# MCU.net
KiCad netlist of a schematic drawn in Altium Designer
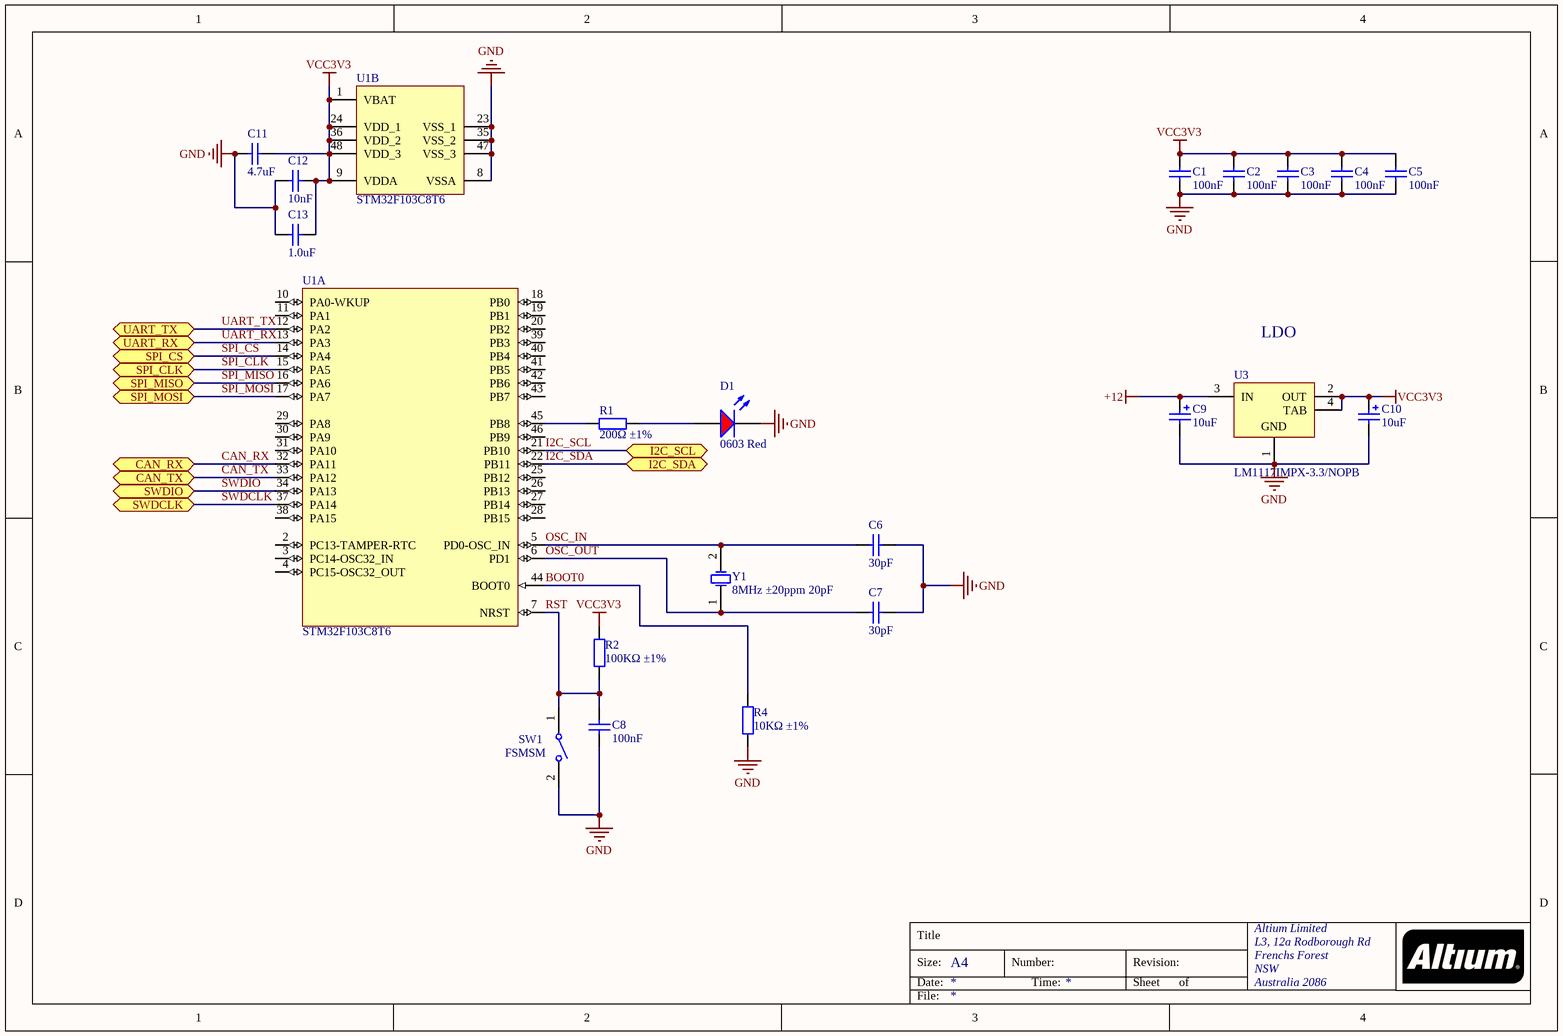
[diagram p0: MCU.SchDoc]

(export (version "E")
  (design (tool "Eeschema 10.0.6"))
  (components
    (comp (ref "C1")
      (value "100nF")
      (footprint "0402_C")
      (description "Chip capacitors")
      (fields
        (field (name "MANUFACTURER") "Samsung Electro-Mechanics")
        (field (name "PARTNUMBER") "CL05B104KO5NNNC")
      )
      (libsource (lib "Miscellaneous Devices LC") (part "0402 100nF (104) 10% 16V"))
    )
    (comp (ref "C2")
      (value "100nF")
      (footprint "0402_C")
      (description "Chip capacitors")
      (fields
        (field (name "MANUFACTURER") "Samsung Electro-Mechanics")
        (field (name "PARTNUMBER") "CL05B104KO5NNNC")
      )
      (libsource (lib "Miscellaneous Devices LC") (part "0402 100nF (104) 10% 16V"))
    )
    (comp (ref "C3")
      (value "100nF")
      (footprint "0402_C")
      (description "Chip capacitors")
      (fields
        (field (name "MANUFACTURER") "Samsung Electro-Mechanics")
        (field (name "PARTNUMBER") "CL05B104KO5NNNC")
      )
      (libsource (lib "Miscellaneous Devices LC") (part "0402 100nF (104) 10% 16V"))
    )
    (comp (ref "C4")
      (value "100nF")
      (footprint "0402_C")
      (description "Chip capacitors")
      (fields
        (field (name "MANUFACTURER") "Samsung Electro-Mechanics")
        (field (name "PARTNUMBER") "CL05B104KO5NNNC")
      )
      (libsource (lib "Miscellaneous Devices LC") (part "0402 100nF (104) 10% 16V"))
    )
    (comp (ref "C5")
      (value "100nF")
      (footprint "0402_C")
      (description "Chip capacitors")
      (fields
        (field (name "MANUFACTURER") "Samsung Electro-Mechanics")
        (field (name "PARTNUMBER") "CL05B104KO5NNNC")
      )
      (libsource (lib "Miscellaneous Devices LC") (part "0402 100nF (104) 10% 16V"))
    )
    (comp (ref "C6")
      (value "30pF")
      (footprint "0402_C")
      (description "Chip capacitors")
      (fields
        (field (name "MANUFACTURER") "Guangdong Fenghua Advanced Tech")
        (field (name "PARTNUMBER") "0402CG300J500NT")
      )
      (libsource (lib "Miscellaneous Devices LC") (part "0402 30pF (300) 5% 50V"))
    )
    (comp (ref "C7")
      (value "30pF")
      (footprint "0402_C")
      (description "Chip capacitors")
      (fields
        (field (name "MANUFACTURER") "Guangdong Fenghua Advanced Tech")
        (field (name "PARTNUMBER") "0402CG300J500NT")
      )
      (libsource (lib "Miscellaneous Devices LC") (part "0402 30pF (300) 5% 50V"))
    )
    (comp (ref "C8")
      (value "100nF")
      (footprint "0402_C")
      (description "Chip capacitors")
      (fields
        (field (name "MANUFACTURER") "Samsung Electro-Mechanics")
        (field (name "PARTNUMBER") "CL05B104KO5NNNC")
      )
      (libsource (lib "Miscellaneous Devices LC") (part "0402 100nF (104) 10% 16V"))
    )
    (comp (ref "C9")
      (value "10uF")
      (footprint "CASE-A_3216")
      (description "Tantalum capacitor")
      (fields (field (name "MANUFACTURER") "AVX") (field (name "PARTNUMBER") "TAJA106K016RNJ"))
      (libsource (lib "Miscellaneous Devices LC") (part "3216 10uF (106) 10% 16V"))
    )
    (comp (ref "C10")
      (value "10uF")
      (footprint "CASE-A_3216")
      (description "Tantalum capacitor")
      (fields (field (name "MANUFACTURER") "AVX") (field (name "PARTNUMBER") "TAJA106K016RNJ"))
      (libsource (lib "Miscellaneous Devices LC") (part "3216 10uF (106) 10% 16V"))
    )
    (comp (ref "C11")
      (value "4.7uF")
      (footprint "0402_C")
      (description "Chip capacitor")
      (fields
        (field (name "MANUFACTURER") "Samsung Electro-Mechanics")
        (field (name "PARTNUMBER") "CL05A475MP5NRNC")
      )
      (libsource (lib "Miscellaneous Devices LC") (part "0402 4.7uF (475) 20% 10V"))
    )
    (comp (ref "C12")
      (value "10nF")
      (footprint "0402_C")
      (description "Chip capacitors")
      (fields
        (field (name "MANUFACTURER") "Samsung Electro-Mechanics")
        (field (name "PARTNUMBER") "CL05B103KB5NNNC")
      )
      (libsource (lib "Miscellaneous Devices LC") (part "0402 10nF (103) 10% 50V"))
    )
    (comp (ref "C13")
      (value "1.0uF")
      (footprint "0402_C")
      (description "Chip capacitor")
      (fields
        (field (name "MANUFACTURER") "Samsung Electro-Mechanics")
        (field (name "PARTNUMBER") "CL05A105KA5NQNC")
      )
      (libsource (lib "Miscellaneous Devices LC") (part "0402 1.0uF (105) 10% 25V"))
    )
    (comp (ref "D1")
      (value "0603 Red")
      (footprint "0603_LED_S1")
      (description "LED")
      (libsource (lib "Miscellaneous Devices LC") (part "0603 LED Red"))
    )
    (comp (ref "R1")
      (value "200Ω ±1%")
      (footprint "0402_R")
      (description "Chip resistor")
      (fields (field (name "MANUFACTURER") "Uniroyal Elec") (field (name "PARTNUMBER") "0402WGF2000TCE"))
      (libsource (lib "Miscellaneous Devices LC") (part "0402 200R (2000) 1%"))
    )
    (comp (ref "R2")
      (value "100KΩ ±1%")
      (footprint "0402_R")
      (description "Chip resistor")
      (fields (field (name "MANUFACTURER") "Uniroyal Elec") (field (name "PARTNUMBER") "0402WGF1003TCE"))
      (libsource (lib "Miscellaneous Devices LC") (part "0402 100K (1003) 1%"))
    )
    (comp (ref "R4")
      (value "10KΩ ±1%")
      (footprint "0402_R")
      (description "Chip resistor")
      (fields (field (name "MANUFACTURER") "Uniroyal Elec") (field (name "PARTNUMBER") "0402WGF1002TCE"))
      (libsource (lib "Miscellaneous Devices LC") (part "0402 10K (1002) 1%"))
    )
    (comp (ref "SW1")
      (value "FSMSM")
      (footprint "TECO-FSMSM-2_V")
      (description "FSMSM Push Button Switch, 50 mA, -35 to 85 degC, 2-Pin SMD, RoHS, Bulk")
      (fields (field (name "MANUFACTURER") "TE Connectivity"))
      (libsource (lib "Altium Content Vault") (part "SW-SPST-2_C"))
    )
    (comp (ref "U1")
      (value "STM32F103C8T6")
      (footprint "LQFP-48_7x7x05P")
      (description "ARM")
      (libsource (lib "Miscellaneous Devices LC") (part "STM32F103C8T6"))
    )
    (comp (ref "U3")
      (value "LM1117IMPX-3.3/NOPB")
      (footprint "MP04A_M")
      (description "800mA Low-Dropout Linear Regulator, 4-pin SOT-223, Pb-Free")
      (fields (field (name "MANUFACTURER") "National Semiconductor"))
      (libsource (lib "Altium Content Vault") (part "PM-REG-LM1086-SOT4"))
    )
    (comp (ref "Y1")
      (value "8MHz ±20ppm 20pF")
      (footprint "SMD-5032_2P")
      (description "贴片晶振")
      (libsource (lib "Miscellaneous Devices LC") (part "SMD-5032_2P 8MHz 20ppm 20pF"))
    )
  )
  (nets
    (net (code "1") (name "+12") (class "Default")
      (node (ref "C9") (pin "1") (pinfunction "1_1") (pintype "passive"))
      (node (ref "U3") (pin "3") (pinfunction "IN_3") (pintype "power_in"))
    )
    (net (code "2") (name "/BOOT0") (class "Default")
      (node (ref "R4") (pin "2") (pinfunction "2_2") (pintype "passive"))
      (node (ref "U1") (pin "44") (pinfunction "BOOT0_44") (pintype "input"))
    )
    (net (code "3") (name "/CAN_RX") (class "Default")
      (node (ref "U1") (pin "32") (pinfunction "PA11_32") (pintype "bidirectional"))
    )
    (net (code "4") (name "/CAN_TX") (class "Default")
      (node (ref "U1") (pin "33") (pinfunction "PA12_33") (pintype "bidirectional"))
    )
    (net (code "5") (name "/I2C_SCL") (class "Default")
      (node (ref "U1") (pin "21") (pinfunction "PB10_21") (pintype "bidirectional"))
    )
    (net (code "6") (name "/I2C_SDA") (class "Default")
      (node (ref "U1") (pin "22") (pinfunction "PB11_22") (pintype "bidirectional"))
    )
    (net (code "7") (name "/OSC_IN") (class "Default")
      (node (ref "C6") (pin "1") (pinfunction "1_1") (pintype "passive"))
      (node (ref "U1") (pin "5") (pinfunction "PD0-OSC_IN_5") (pintype "bidirectional"))
      (node (ref "Y1") (pin "2") (pinfunction "OSC2_2") (pintype "passive"))
    )
    (net (code "8") (name "/OSC_OUT") (class "Default")
      (node (ref "C7") (pin "1") (pinfunction "1_1") (pintype "passive"))
      (node (ref "U1") (pin "6") (pinfunction "PD1_6") (pintype "bidirectional"))
      (node (ref "Y1") (pin "1") (pinfunction "OSC1_1") (pintype "passive"))
    )
    (net (code "9") (name "/RST") (class "Default")
      (node (ref "C8") (pin "2") (pinfunction "2_2") (pintype "passive"))
      (node (ref "R2") (pin "1") (pinfunction "1_1") (pintype "passive"))
      (node (ref "SW1") (pin "1") (pinfunction "1_1") (pintype "passive"))
      (node (ref "U1") (pin "7") (pinfunction "NRST_7") (pintype "bidirectional"))
    )
    (net (code "10") (name "/SPI_CLK") (class "Default")
      (node (ref "U1") (pin "15") (pinfunction "PA5_15") (pintype "bidirectional"))
    )
    (net (code "11") (name "/SPI_CS") (class "Default")
      (node (ref "U1") (pin "14") (pinfunction "PA4_14") (pintype "bidirectional"))
    )
    (net (code "12") (name "/SPI_MISO") (class "Default")
      (node (ref "U1") (pin "16") (pinfunction "PA6_16") (pintype "bidirectional"))
    )
    (net (code "13") (name "/SPI_MOSI") (class "Default")
      (node (ref "U1") (pin "17") (pinfunction "PA7_17") (pintype "bidirectional"))
    )
    (net (code "14") (name "/SWDCLK") (class "Default")
      (node (ref "U1") (pin "37") (pinfunction "PA14_37") (pintype "bidirectional"))
    )
    (net (code "15") (name "/SWDIO") (class "Default")
      (node (ref "U1") (pin "34") (pinfunction "PA13_34") (pintype "bidirectional"))
    )
    (net (code "16") (name "/UART_RX") (class "Default")
      (node (ref "U1") (pin "13") (pinfunction "PA3_13") (pintype "bidirectional"))
    )
    (net (code "17") (name "/UART_TX") (class "Default")
      (node (ref "U1") (pin "12") (pinfunction "PA2_12") (pintype "bidirectional"))
    )
    (net (code "18") (name "GND") (class "Default")
      (node (ref "C1") (pin "1") (pinfunction "1_1") (pintype "passive"))
      (node (ref "C10") (pin "2") (pinfunction "2_2") (pintype "passive"))
      (node (ref "C11") (pin "1") (pinfunction "1_1") (pintype "passive"))
      (node (ref "C12") (pin "1") (pinfunction "1_1") (pintype "passive"))
      (node (ref "C13") (pin "1") (pinfunction "1_1") (pintype "passive"))
      (node (ref "C2") (pin "1") (pinfunction "1_1") (pintype "passive"))
      (node (ref "C3") (pin "1") (pinfunction "1_1") (pintype "passive"))
      (node (ref "C4") (pin "1") (pinfunction "1_1") (pintype "passive"))
      (node (ref "C5") (pin "1") (pinfunction "1_1") (pintype "passive"))
      (node (ref "C6") (pin "2") (pinfunction "2_2") (pintype "passive"))
      (node (ref "C7") (pin "2") (pinfunction "2_2") (pintype "passive"))
      (node (ref "C8") (pin "1") (pinfunction "1_1") (pintype "passive"))
      (node (ref "C9") (pin "2") (pinfunction "2_2") (pintype "passive"))
      (node (ref "D1") (pin "K") (pinfunction "K_K") (pintype "passive"))
      (node (ref "R4") (pin "1") (pinfunction "1_1") (pintype "passive"))
      (node (ref "SW1") (pin "2") (pinfunction "2_2") (pintype "passive"))
      (node (ref "U1") (pin "23") (pinfunction "VSS_1_23") (pintype "power_in"))
      (node (ref "U1") (pin "35") (pinfunction "VSS_2_35") (pintype "power_in"))
      (node (ref "U1") (pin "47") (pinfunction "VSS_3_47") (pintype "power_in"))
      (node (ref "U1") (pin "8") (pinfunction "VSSA_8") (pintype "power_in"))
      (node (ref "U3") (pin "1") (pinfunction "GND_1") (pintype "power_in"))
    )
    (net (code "19") (name "Net-(D1-PadA)") (class "Default")
      (node (ref "D1") (pin "A") (pinfunction "A_A") (pintype "passive"))
      (node (ref "R1") (pin "2") (pinfunction "2_2") (pintype "passive"))
    )
    (net (code "20") (name "Net-(U1A-PB8)") (class "Default")
      (node (ref "R1") (pin "1") (pinfunction "1_1") (pintype "passive"))
      (node (ref "U1") (pin "45") (pinfunction "PB8_45") (pintype "bidirectional"))
    )
    (net (code "21") (name "VCC3V3") (class "Default")
      (node (ref "C1") (pin "2") (pinfunction "2_2") (pintype "passive"))
      (node (ref "C10") (pin "1") (pinfunction "1_1") (pintype "passive"))
      (node (ref "C11") (pin "2") (pinfunction "2_2") (pintype "passive"))
      (node (ref "C12") (pin "2") (pinfunction "2_2") (pintype "passive"))
      (node (ref "C13") (pin "2") (pinfunction "2_2") (pintype "passive"))
      (node (ref "C2") (pin "2") (pinfunction "2_2") (pintype "passive"))
      (node (ref "C3") (pin "2") (pinfunction "2_2") (pintype "passive"))
      (node (ref "C4") (pin "2") (pinfunction "2_2") (pintype "passive"))
      (node (ref "C5") (pin "2") (pinfunction "2_2") (pintype "passive"))
      (node (ref "R2") (pin "2") (pinfunction "2_2") (pintype "passive"))
      (node (ref "U1") (pin "1") (pinfunction "VBAT_1") (pintype "power_in"))
      (node (ref "U1") (pin "24") (pinfunction "VDD_1_24") (pintype "power_in"))
      (node (ref "U1") (pin "36") (pinfunction "VDD_2_36") (pintype "power_in"))
      (node (ref "U1") (pin "48") (pinfunction "VDD_3_48") (pintype "power_in"))
      (node (ref "U1") (pin "9") (pinfunction "VDDA_9") (pintype "power_in"))
      (node (ref "U3") (pin "2") (pinfunction "OUT_2") (pintype "power_in"))
      (node (ref "U3") (pin "4") (pinfunction "TAB_4") (pintype "power_in"))
    )
    (net (code "22") (name "unconnected-(U1A-PA0-WKUP-Pad10)") (class "Default")
      (node (ref "U1") (pin "10") (pinfunction "PA0-WKUP_10") (pintype "bidirectional"))
    )
    (net (code "23") (name "unconnected-(U1A-PA1-Pad11)") (class "Default")
      (node (ref "U1") (pin "11") (pinfunction "PA1_11") (pintype "bidirectional"))
    )
    (net (code "24") (name "unconnected-(U1A-PA8-Pad29)") (class "Default")
      (node (ref "U1") (pin "29") (pinfunction "PA8_29") (pintype "bidirectional"))
    )
    (net (code "25") (name "unconnected-(U1A-PA9-Pad30)") (class "Default")
      (node (ref "U1") (pin "30") (pinfunction "PA9_30") (pintype "bidirectional"))
    )
    (net (code "26") (name "unconnected-(U1A-PA10-Pad31)") (class "Default")
      (node (ref "U1") (pin "31") (pinfunction "PA10_31") (pintype "bidirectional"))
    )
    (net (code "27") (name "unconnected-(U1A-PA15-Pad38)") (class "Default")
      (node (ref "U1") (pin "38") (pinfunction "PA15_38") (pintype "bidirectional"))
    )
    (net (code "28") (name "unconnected-(U1A-PB0-Pad18)") (class "Default")
      (node (ref "U1") (pin "18") (pinfunction "PB0_18") (pintype "bidirectional"))
    )
    (net (code "29") (name "unconnected-(U1A-PB1-Pad19)") (class "Default")
      (node (ref "U1") (pin "19") (pinfunction "PB1_19") (pintype "bidirectional"))
    )
    (net (code "30") (name "unconnected-(U1A-PB2-Pad20)") (class "Default")
      (node (ref "U1") (pin "20") (pinfunction "PB2_20") (pintype "bidirectional"))
    )
    (net (code "31") (name "unconnected-(U1A-PB3-Pad39)") (class "Default")
      (node (ref "U1") (pin "39") (pinfunction "PB3_39") (pintype "bidirectional"))
    )
    (net (code "32") (name "unconnected-(U1A-PB4-Pad40)") (class "Default")
      (node (ref "U1") (pin "40") (pinfunction "PB4_40") (pintype "bidirectional"))
    )
    (net (code "33") (name "unconnected-(U1A-PB5-Pad41)") (class "Default")
      (node (ref "U1") (pin "41") (pinfunction "PB5_41") (pintype "bidirectional"))
    )
    (net (code "34") (name "unconnected-(U1A-PB6-Pad42)") (class "Default")
      (node (ref "U1") (pin "42") (pinfunction "PB6_42") (pintype "bidirectional"))
    )
    (net (code "35") (name "unconnected-(U1A-PB7-Pad43)") (class "Default")
      (node (ref "U1") (pin "43") (pinfunction "PB7_43") (pintype "bidirectional"))
    )
    (net (code "36") (name "unconnected-(U1A-PB9-Pad46)") (class "Default")
      (node (ref "U1") (pin "46") (pinfunction "PB9_46") (pintype "bidirectional"))
    )
    (net (code "37") (name "unconnected-(U1A-PB12-Pad25)") (class "Default")
      (node (ref "U1") (pin "25") (pinfunction "PB12_25") (pintype "bidirectional"))
    )
    (net (code "38") (name "unconnected-(U1A-PB13-Pad26)") (class "Default")
      (node (ref "U1") (pin "26") (pinfunction "PB13_26") (pintype "bidirectional"))
    )
    (net (code "39") (name "unconnected-(U1A-PB14-Pad27)") (class "Default")
      (node (ref "U1") (pin "27") (pinfunction "PB14_27") (pintype "bidirectional"))
    )
    (net (code "40") (name "unconnected-(U1A-PB15-Pad28)") (class "Default")
      (node (ref "U1") (pin "28") (pinfunction "PB15_28") (pintype "bidirectional"))
    )
    (net (code "41") (name "unconnected-(U1A-PC13-TAMPER-RTC-Pad2)") (class "Default")
      (node (ref "U1") (pin "2") (pinfunction "PC13-TAMPER-RTC_2") (pintype "bidirectional"))
    )
    (net (code "42") (name "unconnected-(U1A-PC14-OSC32_IN-Pad3)") (class "Default")
      (node (ref "U1") (pin "3") (pinfunction "PC14-OSC32_IN_3") (pintype "bidirectional"))
    )
    (net (code "43") (name "unconnected-(U1A-PC15-OSC32_OUT-Pad4)") (class "Default")
      (node (ref "U1") (pin "4") (pinfunction "PC15-OSC32_OUT_4") (pintype "bidirectional"))
    )
  )
)
